# wireless_modul_board.net
KiCad netlist of a schematic drawn in EAGLE
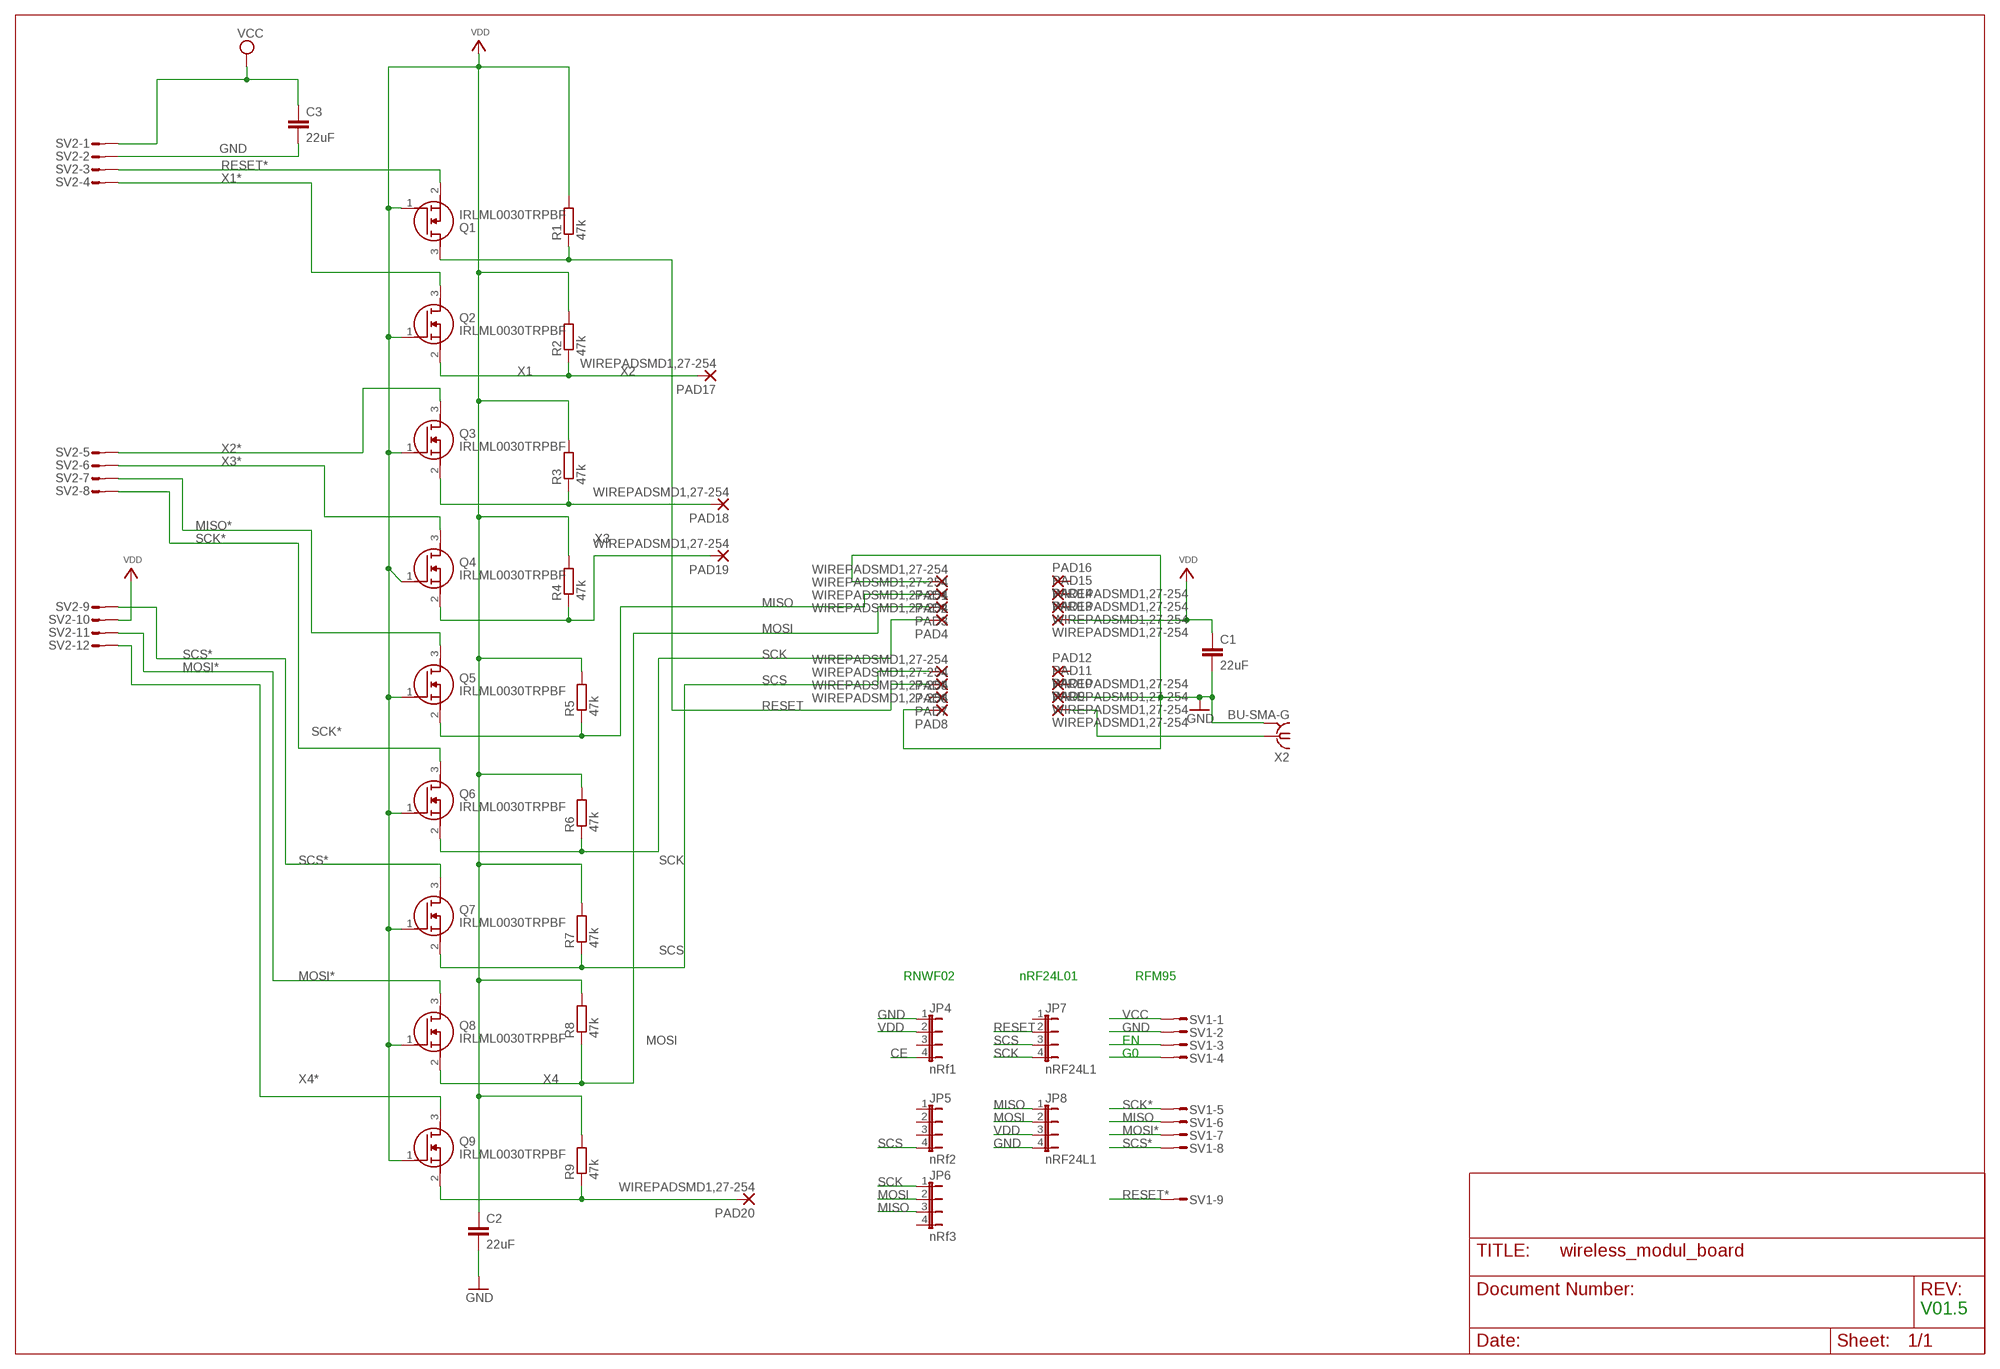
[diagram p0: schematic, sheet 1]

(export (version "E")
  (design (tool "Eeschema 10.0.6"))
  (components
    (comp (ref "C1")
      (value "22uF")
      (footprint "eagle-import:C1206")
      (libsource (lib "eagle-import") (part "C-EUC1206"))
    )
    (comp (ref "C2")
      (value "22uF")
      (footprint "eagle-import:C1206")
      (libsource (lib "eagle-import") (part "C-EUC1206"))
    )
    (comp (ref "C3")
      (value "22uF")
      (footprint "eagle-import:C1206")
      (libsource (lib "eagle-import") (part "C-EUC1206"))
    )
    (comp (ref "JP4")
      (value "nRf1")
      (footprint "eagle-import:JP4")
      (libsource (lib "eagle-import") (part "JP4E"))
    )
    (comp (ref "JP5")
      (value "nRf2")
      (footprint "eagle-import:JP4")
      (libsource (lib "eagle-import") (part "JP4E"))
    )
    (comp (ref "JP6")
      (value "nRf3")
      (footprint "eagle-import:JP4")
      (libsource (lib "eagle-import") (part "JP4E"))
    )
    (comp (ref "JP7")
      (value "nRF24L1")
      (footprint "eagle-import:JP4")
      (libsource (lib "eagle-import") (part "JP4E"))
    )
    (comp (ref "JP8")
      (value "nRF24L1")
      (footprint "eagle-import:JP4")
      (libsource (lib "eagle-import") (part "JP4E"))
    )
    (comp (ref "PAD1")
      (value "WIREPADSMD1,27-254")
      (footprint "eagle-import:SMD1,27-2,54")
      (libsource (lib "eagle-import") (part "WIREPADSMD1,27-254"))
    )
    (comp (ref "PAD2")
      (value "WIREPADSMD1,27-254")
      (footprint "eagle-import:SMD1,27-2,54")
      (libsource (lib "eagle-import") (part "WIREPADSMD1,27-254"))
    )
    (comp (ref "PAD3")
      (value "WIREPADSMD1,27-254")
      (footprint "eagle-import:SMD1,27-2,54")
      (libsource (lib "eagle-import") (part "WIREPADSMD1,27-254"))
    )
    (comp (ref "PAD4")
      (value "WIREPADSMD1,27-254")
      (footprint "eagle-import:SMD1,27-2,54")
      (libsource (lib "eagle-import") (part "WIREPADSMD1,27-254"))
    )
    (comp (ref "PAD5")
      (value "WIREPADSMD1,27-254")
      (footprint "eagle-import:SMD1,27-2,54")
      (libsource (lib "eagle-import") (part "WIREPADSMD1,27-254"))
    )
    (comp (ref "PAD6")
      (value "WIREPADSMD1,27-254")
      (footprint "eagle-import:SMD1,27-2,54")
      (libsource (lib "eagle-import") (part "WIREPADSMD1,27-254"))
    )
    (comp (ref "PAD7")
      (value "WIREPADSMD1,27-254")
      (footprint "eagle-import:SMD1,27-2,54")
      (libsource (lib "eagle-import") (part "WIREPADSMD1,27-254"))
    )
    (comp (ref "PAD8")
      (value "WIREPADSMD1,27-254")
      (footprint "eagle-import:SMD1,27-2,54")
      (libsource (lib "eagle-import") (part "WIREPADSMD1,27-254"))
    )
    (comp (ref "PAD9")
      (value "WIREPADSMD1,27-254")
      (footprint "eagle-import:SMD1,27-2,54")
      (libsource (lib "eagle-import") (part "WIREPADSMD1,27-254"))
    )
    (comp (ref "PAD10")
      (value "WIREPADSMD1,27-254")
      (footprint "eagle-import:SMD1,27-2,54")
      (libsource (lib "eagle-import") (part "WIREPADSMD1,27-254"))
    )
    (comp (ref "PAD11")
      (value "WIREPADSMD1,27-254")
      (footprint "eagle-import:SMD1,27-2,54")
      (libsource (lib "eagle-import") (part "WIREPADSMD1,27-254"))
    )
    (comp (ref "PAD12")
      (value "WIREPADSMD1,27-254")
      (footprint "eagle-import:SMD1,27-2,54")
      (libsource (lib "eagle-import") (part "WIREPADSMD1,27-254"))
    )
    (comp (ref "PAD13")
      (value "WIREPADSMD1,27-254")
      (footprint "eagle-import:SMD1,27-2,54")
      (libsource (lib "eagle-import") (part "WIREPADSMD1,27-254"))
    )
    (comp (ref "PAD14")
      (value "WIREPADSMD1,27-254")
      (footprint "eagle-import:SMD1,27-2,54")
      (libsource (lib "eagle-import") (part "WIREPADSMD1,27-254"))
    )
    (comp (ref "PAD15")
      (value "WIREPADSMD1,27-254")
      (footprint "eagle-import:SMD1,27-2,54")
      (libsource (lib "eagle-import") (part "WIREPADSMD1,27-254"))
    )
    (comp (ref "PAD16")
      (value "WIREPADSMD1,27-254")
      (footprint "eagle-import:SMD1,27-2,54")
      (libsource (lib "eagle-import") (part "WIREPADSMD1,27-254"))
    )
    (comp (ref "PAD17")
      (value "WIREPADSMD1,27-254")
      (footprint "eagle-import:SMD1,27-2,54")
      (libsource (lib "eagle-import") (part "WIREPADSMD1,27-254"))
    )
    (comp (ref "PAD18")
      (value "WIREPADSMD1,27-254")
      (footprint "eagle-import:SMD1,27-2,54")
      (libsource (lib "eagle-import") (part "WIREPADSMD1,27-254"))
    )
    (comp (ref "PAD19")
      (value "WIREPADSMD1,27-254")
      (footprint "eagle-import:SMD1,27-2,54")
      (libsource (lib "eagle-import") (part "WIREPADSMD1,27-254"))
    )
    (comp (ref "PAD20")
      (value "WIREPADSMD1,27-254")
      (footprint "eagle-import:SMD1,27-2,54")
      (libsource (lib "eagle-import") (part "WIREPADSMD1,27-254"))
    )
    (comp (ref "Q1")
      (value "IRLML0030TRPBF")
      (footprint "eagle-import:SOT95P237X112-3N")
      (fields (field (name "MF") "Infineon Technologies"))
      (libsource (lib "eagle-import") (part "IRLML0030TRPBF"))
    )
    (comp (ref "Q2")
      (value "IRLML0030TRPBF")
      (footprint "eagle-import:SOT95P237X112-3N")
      (fields (field (name "MF") "Infineon Technologies"))
      (libsource (lib "eagle-import") (part "IRLML0030TRPBF"))
    )
    (comp (ref "Q3")
      (value "IRLML0030TRPBF")
      (footprint "eagle-import:SOT95P237X112-3N")
      (fields (field (name "MF") "Infineon Technologies"))
      (libsource (lib "eagle-import") (part "IRLML0030TRPBF"))
    )
    (comp (ref "Q4")
      (value "IRLML0030TRPBF")
      (footprint "eagle-import:SOT95P237X112-3N")
      (fields (field (name "MF") "Infineon Technologies"))
      (libsource (lib "eagle-import") (part "IRLML0030TRPBF"))
    )
    (comp (ref "Q5")
      (value "IRLML0030TRPBF")
      (footprint "eagle-import:SOT95P237X112-3N")
      (fields (field (name "MF") "Infineon Technologies"))
      (libsource (lib "eagle-import") (part "IRLML0030TRPBF"))
    )
    (comp (ref "Q6")
      (value "IRLML0030TRPBF")
      (footprint "eagle-import:SOT95P237X112-3N")
      (fields (field (name "MF") "Infineon Technologies"))
      (libsource (lib "eagle-import") (part "IRLML0030TRPBF"))
    )
    (comp (ref "Q7")
      (value "IRLML0030TRPBF")
      (footprint "eagle-import:SOT95P237X112-3N")
      (fields (field (name "MF") "Infineon Technologies"))
      (libsource (lib "eagle-import") (part "IRLML0030TRPBF"))
    )
    (comp (ref "Q8")
      (value "IRLML0030TRPBF")
      (footprint "eagle-import:SOT95P237X112-3N")
      (fields (field (name "MF") "Infineon Technologies"))
      (libsource (lib "eagle-import") (part "IRLML0030TRPBF"))
    )
    (comp (ref "Q9")
      (value "IRLML0030TRPBF")
      (footprint "eagle-import:SOT95P237X112-3N")
      (fields (field (name "MF") "Infineon Technologies"))
      (libsource (lib "eagle-import") (part "IRLML0030TRPBF"))
    )
    (comp (ref "R1")
      (value "47k")
      (footprint "eagle-import:R1206")
      (libsource (lib "eagle-import") (part "R-EU_R1206"))
    )
    (comp (ref "R2")
      (value "47k")
      (footprint "eagle-import:R1206")
      (libsource (lib "eagle-import") (part "R-EU_R1206"))
    )
    (comp (ref "R3")
      (value "47k")
      (footprint "eagle-import:R1206")
      (libsource (lib "eagle-import") (part "R-EU_R1206"))
    )
    (comp (ref "R4")
      (value "47k")
      (footprint "eagle-import:R1206")
      (libsource (lib "eagle-import") (part "R-EU_R1206"))
    )
    (comp (ref "R5")
      (value "47k")
      (footprint "eagle-import:R1206")
      (libsource (lib "eagle-import") (part "R-EU_R1206"))
    )
    (comp (ref "R6")
      (value "47k")
      (footprint "eagle-import:R1206")
      (libsource (lib "eagle-import") (part "R-EU_R1206"))
    )
    (comp (ref "R7")
      (value "47k")
      (footprint "eagle-import:R1206")
      (libsource (lib "eagle-import") (part "R-EU_R1206"))
    )
    (comp (ref "R8")
      (value "47k")
      (footprint "eagle-import:R1206")
      (libsource (lib "eagle-import") (part "R-EU_R1206"))
    )
    (comp (ref "R9")
      (value "47k")
      (footprint "eagle-import:R1206")
      (libsource (lib "eagle-import") (part "R-EU_R1206"))
    )
    (comp (ref "SV1")
      (value "S09P")
      (footprint "eagle-import:S09P")
      (libsource (lib "eagle-import") (part "S09P"))
    )
    (comp (ref "SV2")
      (value "S12P")
      (footprint "eagle-import:S12P")
      (libsource (lib "eagle-import") (part "S12P"))
    )
    (comp (ref "X2")
      (value "BU-SMA-G")
      (footprint "eagle-import:BU-SMA-G")
      (libsource (lib "eagle-import") (part "BU-SMA-G"))
    )
  )
  (nets
    (net (code "1") (name "/CE") (class "Default")
      (node (ref "JP4") (pin "4") (pinfunction "4_4") (pintype "passive"))
    )
    (net (code "2") (name "/MISO") (class "Default")
      (node (ref "JP6") (pin "3") (pinfunction "3_3") (pintype "passive"))
      (node (ref "JP8") (pin "1") (pinfunction "1_1") (pintype "passive"))
      (node (ref "PAD2") (pin "1") (pinfunction "P_1") (pintype "passive"))
      (node (ref "Q5") (pin "2") (pinfunction "S_2") (pintype "bidirectional"))
      (node (ref "R5") (pin "1") (pinfunction "1_1") (pintype "passive"))
      (node (ref "SV1") (pin "6") (pinfunction "S_6") (pintype "passive"))
    )
    (net (code "3") (name "/MISO*") (class "Default")
      (node (ref "Q5") (pin "3") (pinfunction "D_3") (pintype "bidirectional"))
      (node (ref "SV2") (pin "7") (pinfunction "S_7") (pintype "passive"))
    )
    (net (code "4") (name "/MOSI") (class "Default")
      (node (ref "JP6") (pin "2") (pinfunction "2_2") (pintype "passive"))
      (node (ref "JP8") (pin "2") (pinfunction "2_2") (pintype "passive"))
      (node (ref "PAD3") (pin "1") (pinfunction "P_1") (pintype "passive"))
      (node (ref "Q8") (pin "2") (pinfunction "S_2") (pintype "bidirectional"))
      (node (ref "R8") (pin "1") (pinfunction "1_1") (pintype "passive"))
    )
    (net (code "5") (name "/MOSI*") (class "Default")
      (node (ref "Q8") (pin "3") (pinfunction "D_3") (pintype "bidirectional"))
      (node (ref "SV1") (pin "7") (pinfunction "S_7") (pintype "passive"))
      (node (ref "SV2") (pin "11") (pinfunction "S_11") (pintype "passive"))
    )
    (net (code "6") (name "/RESET") (class "Default")
      (node (ref "JP7") (pin "2") (pinfunction "2_2") (pintype "passive"))
      (node (ref "PAD6") (pin "1") (pinfunction "P_1") (pintype "passive"))
      (node (ref "Q1") (pin "3") (pinfunction "D_3") (pintype "bidirectional"))
      (node (ref "R1") (pin "1") (pinfunction "1_1") (pintype "passive"))
    )
    (net (code "7") (name "/RESET*") (class "Default")
      (node (ref "Q1") (pin "2") (pinfunction "S_2") (pintype "bidirectional"))
      (node (ref "SV1") (pin "9") (pinfunction "S_9") (pintype "passive"))
      (node (ref "SV2") (pin "3") (pinfunction "S_3") (pintype "passive"))
    )
    (net (code "8") (name "/SCK") (class "Default")
      (node (ref "JP6") (pin "1") (pinfunction "1_1") (pintype "passive"))
      (node (ref "JP7") (pin "4") (pinfunction "4_4") (pintype "passive"))
      (node (ref "PAD4") (pin "1") (pinfunction "P_1") (pintype "passive"))
      (node (ref "Q6") (pin "2") (pinfunction "S_2") (pintype "bidirectional"))
      (node (ref "R6") (pin "1") (pinfunction "1_1") (pintype "passive"))
    )
    (net (code "9") (name "/SCK*") (class "Default")
      (node (ref "Q6") (pin "3") (pinfunction "D_3") (pintype "bidirectional"))
      (node (ref "SV1") (pin "5") (pinfunction "S_5") (pintype "passive"))
      (node (ref "SV2") (pin "8") (pinfunction "S_8") (pintype "passive"))
    )
    (net (code "10") (name "/SCS") (class "Default")
      (node (ref "JP5") (pin "4") (pinfunction "4_4") (pintype "passive"))
      (node (ref "JP7") (pin "3") (pinfunction "3_3") (pintype "passive"))
      (node (ref "PAD5") (pin "1") (pinfunction "P_1") (pintype "passive"))
      (node (ref "Q7") (pin "2") (pinfunction "S_2") (pintype "bidirectional"))
      (node (ref "R7") (pin "1") (pinfunction "1_1") (pintype "passive"))
    )
    (net (code "11") (name "/SCS*") (class "Default")
      (node (ref "Q7") (pin "3") (pinfunction "D_3") (pintype "bidirectional"))
      (node (ref "SV1") (pin "8") (pinfunction "S_8") (pintype "passive"))
      (node (ref "SV2") (pin "9") (pinfunction "S_9") (pintype "passive"))
    )
    (net (code "12") (name "/X1") (class "Default")
      (node (ref "PAD17") (pin "1") (pinfunction "P_1") (pintype "passive"))
      (node (ref "Q2") (pin "2") (pinfunction "S_2") (pintype "bidirectional"))
      (node (ref "R2") (pin "1") (pinfunction "1_1") (pintype "passive"))
    )
    (net (code "13") (name "/X1*") (class "Default")
      (node (ref "Q2") (pin "3") (pinfunction "D_3") (pintype "bidirectional"))
      (node (ref "SV2") (pin "4") (pinfunction "S_4") (pintype "passive"))
    )
    (net (code "14") (name "/X2") (class "Default")
      (node (ref "PAD18") (pin "1") (pinfunction "P_1") (pintype "passive"))
      (node (ref "Q3") (pin "2") (pinfunction "S_2") (pintype "bidirectional"))
      (node (ref "R3") (pin "1") (pinfunction "1_1") (pintype "passive"))
    )
    (net (code "15") (name "/X2*") (class "Default")
      (node (ref "Q3") (pin "3") (pinfunction "D_3") (pintype "bidirectional"))
      (node (ref "SV2") (pin "5") (pinfunction "S_5") (pintype "passive"))
    )
    (net (code "16") (name "/X3") (class "Default")
      (node (ref "PAD19") (pin "1") (pinfunction "P_1") (pintype "passive"))
      (node (ref "Q4") (pin "2") (pinfunction "S_2") (pintype "bidirectional"))
      (node (ref "R4") (pin "1") (pinfunction "1_1") (pintype "passive"))
    )
    (net (code "17") (name "/X3*") (class "Default")
      (node (ref "Q4") (pin "3") (pinfunction "D_3") (pintype "bidirectional"))
      (node (ref "SV2") (pin "6") (pinfunction "S_6") (pintype "passive"))
    )
    (net (code "18") (name "/X4") (class "Default")
      (node (ref "PAD20") (pin "1") (pinfunction "P_1") (pintype "passive"))
      (node (ref "Q9") (pin "2") (pinfunction "S_2") (pintype "bidirectional"))
      (node (ref "R9") (pin "1") (pinfunction "1_1") (pintype "passive"))
    )
    (net (code "19") (name "/X4*") (class "Default")
      (node (ref "Q9") (pin "3") (pinfunction "D_3") (pintype "bidirectional"))
      (node (ref "SV2") (pin "12") (pinfunction "S_12") (pintype "passive"))
    )
    (net (code "20") (name "GND") (class "Default")
      (node (ref "C1") (pin "2") (pinfunction "2_2") (pintype "passive"))
      (node (ref "C2") (pin "2") (pinfunction "2_2") (pintype "passive"))
      (node (ref "C3") (pin "2") (pinfunction "2_2") (pintype "passive"))
      (node (ref "JP4") (pin "1") (pinfunction "1_1") (pintype "passive"))
      (node (ref "JP8") (pin "4") (pinfunction "4_4") (pintype "passive"))
      (node (ref "PAD1") (pin "1") (pinfunction "P_1") (pintype "passive"))
      (node (ref "PAD10") (pin "1") (pinfunction "P_1") (pintype "passive"))
      (node (ref "PAD8") (pin "1") (pinfunction "P_1") (pintype "passive"))
      (node (ref "SV1") (pin "2") (pinfunction "S_2") (pintype "passive"))
      (node (ref "SV2") (pin "2") (pinfunction "S_2") (pintype "passive"))
      (node (ref "X2") (pin "2") (pinfunction "2_2") (pintype "passive"))
      (node (ref "X2") (pin "3") (pinfunction "2_3") (pintype "passive"))
      (node (ref "X2") (pin "4") (pinfunction "2_4") (pintype "passive"))
      (node (ref "X2") (pin "5") (pinfunction "2_5") (pintype "passive"))
    )
    (net (code "21") (name "Net-(PAD9-P)") (class "Default")
      (node (ref "PAD9") (pin "1") (pinfunction "P_1") (pintype "passive"))
      (node (ref "X2") (pin "1") (pinfunction "1_1") (pintype "passive"))
    )
    (net (code "22") (name "VCC") (class "Default")
      (node (ref "C3") (pin "1") (pinfunction "1_1") (pintype "passive"))
      (node (ref "SV1") (pin "1") (pinfunction "S_1") (pintype "passive"))
      (node (ref "SV2") (pin "1") (pinfunction "S_1") (pintype "passive"))
    )
    (net (code "23") (name "VDD") (class "Default")
      (node (ref "C1") (pin "1") (pinfunction "1_1") (pintype "passive"))
      (node (ref "C2") (pin "1") (pinfunction "1_1") (pintype "passive"))
      (node (ref "JP4") (pin "2") (pinfunction "2_2") (pintype "passive"))
      (node (ref "JP8") (pin "3") (pinfunction "3_3") (pintype "passive"))
      (node (ref "PAD13") (pin "1") (pinfunction "P_1") (pintype "passive"))
      (node (ref "Q1") (pin "1") (pinfunction "G_1") (pintype "input"))
      (node (ref "Q2") (pin "1") (pinfunction "G_1") (pintype "input"))
      (node (ref "Q3") (pin "1") (pinfunction "G_1") (pintype "input"))
      (node (ref "Q4") (pin "1") (pinfunction "G_1") (pintype "input"))
      (node (ref "Q5") (pin "1") (pinfunction "G_1") (pintype "input"))
      (node (ref "Q6") (pin "1") (pinfunction "G_1") (pintype "input"))
      (node (ref "Q7") (pin "1") (pinfunction "G_1") (pintype "input"))
      (node (ref "Q8") (pin "1") (pinfunction "G_1") (pintype "input"))
      (node (ref "Q9") (pin "1") (pinfunction "G_1") (pintype "input"))
      (node (ref "R1") (pin "2") (pinfunction "2_2") (pintype "passive"))
      (node (ref "R2") (pin "2") (pinfunction "2_2") (pintype "passive"))
      (node (ref "R3") (pin "2") (pinfunction "2_2") (pintype "passive"))
      (node (ref "R4") (pin "2") (pinfunction "2_2") (pintype "passive"))
      (node (ref "R5") (pin "2") (pinfunction "2_2") (pintype "passive"))
      (node (ref "R6") (pin "2") (pinfunction "2_2") (pintype "passive"))
      (node (ref "R7") (pin "2") (pinfunction "2_2") (pintype "passive"))
      (node (ref "R8") (pin "2") (pinfunction "2_2") (pintype "passive"))
      (node (ref "R9") (pin "2") (pinfunction "2_2") (pintype "passive"))
      (node (ref "SV2") (pin "10") (pinfunction "S_10") (pintype "passive"))
    )
    (net (code "24") (name "unconnected-(JP4-Pad3)") (class "Default")
      (node (ref "JP4") (pin "3") (pinfunction "3_3") (pintype "passive"))
    )
    (net (code "25") (name "unconnected-(JP5-Pad1)") (class "Default")
      (node (ref "JP5") (pin "1") (pinfunction "1_1") (pintype "passive"))
    )
    (net (code "26") (name "unconnected-(JP5-Pad2)") (class "Default")
      (node (ref "JP5") (pin "2") (pinfunction "2_2") (pintype "passive"))
    )
    (net (code "27") (name "unconnected-(JP5-Pad3)") (class "Default")
      (node (ref "JP5") (pin "3") (pinfunction "3_3") (pintype "passive"))
    )
    (net (code "28") (name "unconnected-(JP6-Pad4)") (class "Default")
      (node (ref "JP6") (pin "4") (pinfunction "4_4") (pintype "passive"))
    )
    (net (code "29") (name "unconnected-(JP7-Pad1)") (class "Default")
      (node (ref "JP7") (pin "1") (pinfunction "1_1") (pintype "passive"))
    )
    (net (code "30") (name "unconnected-(PAD7-P-Pad1)") (class "Default")
      (node (ref "PAD7") (pin "1") (pinfunction "P_1") (pintype "passive"))
    )
    (net (code "31") (name "unconnected-(PAD11-P-Pad1)") (class "Default")
      (node (ref "PAD11") (pin "1") (pinfunction "P_1") (pintype "passive"))
    )
    (net (code "32") (name "unconnected-(PAD12-P-Pad1)") (class "Default")
      (node (ref "PAD12") (pin "1") (pinfunction "P_1") (pintype "passive"))
    )
    (net (code "33") (name "unconnected-(PAD14-P-Pad1)") (class "Default")
      (node (ref "PAD14") (pin "1") (pinfunction "P_1") (pintype "passive"))
    )
    (net (code "34") (name "unconnected-(PAD15-P-Pad1)") (class "Default")
      (node (ref "PAD15") (pin "1") (pinfunction "P_1") (pintype "passive"))
    )
    (net (code "35") (name "unconnected-(PAD16-P-Pad1)") (class "Default")
      (node (ref "PAD16") (pin "1") (pinfunction "P_1") (pintype "passive"))
    )
    (net (code "36") (name "unconnected-(SV1C-S-Pad3)") (class "Default")
      (node (ref "SV1") (pin "3") (pinfunction "S_3") (pintype "passive"))
    )
    (net (code "37") (name "unconnected-(SV1D-S-Pad4)") (class "Default")
      (node (ref "SV1") (pin "4") (pinfunction "S_4") (pintype "passive"))
    )
  )
)
